# RGBW_LED-Band_Treiber_ungueltig.net
KiCad netlist of a schematic drawn in EAGLE
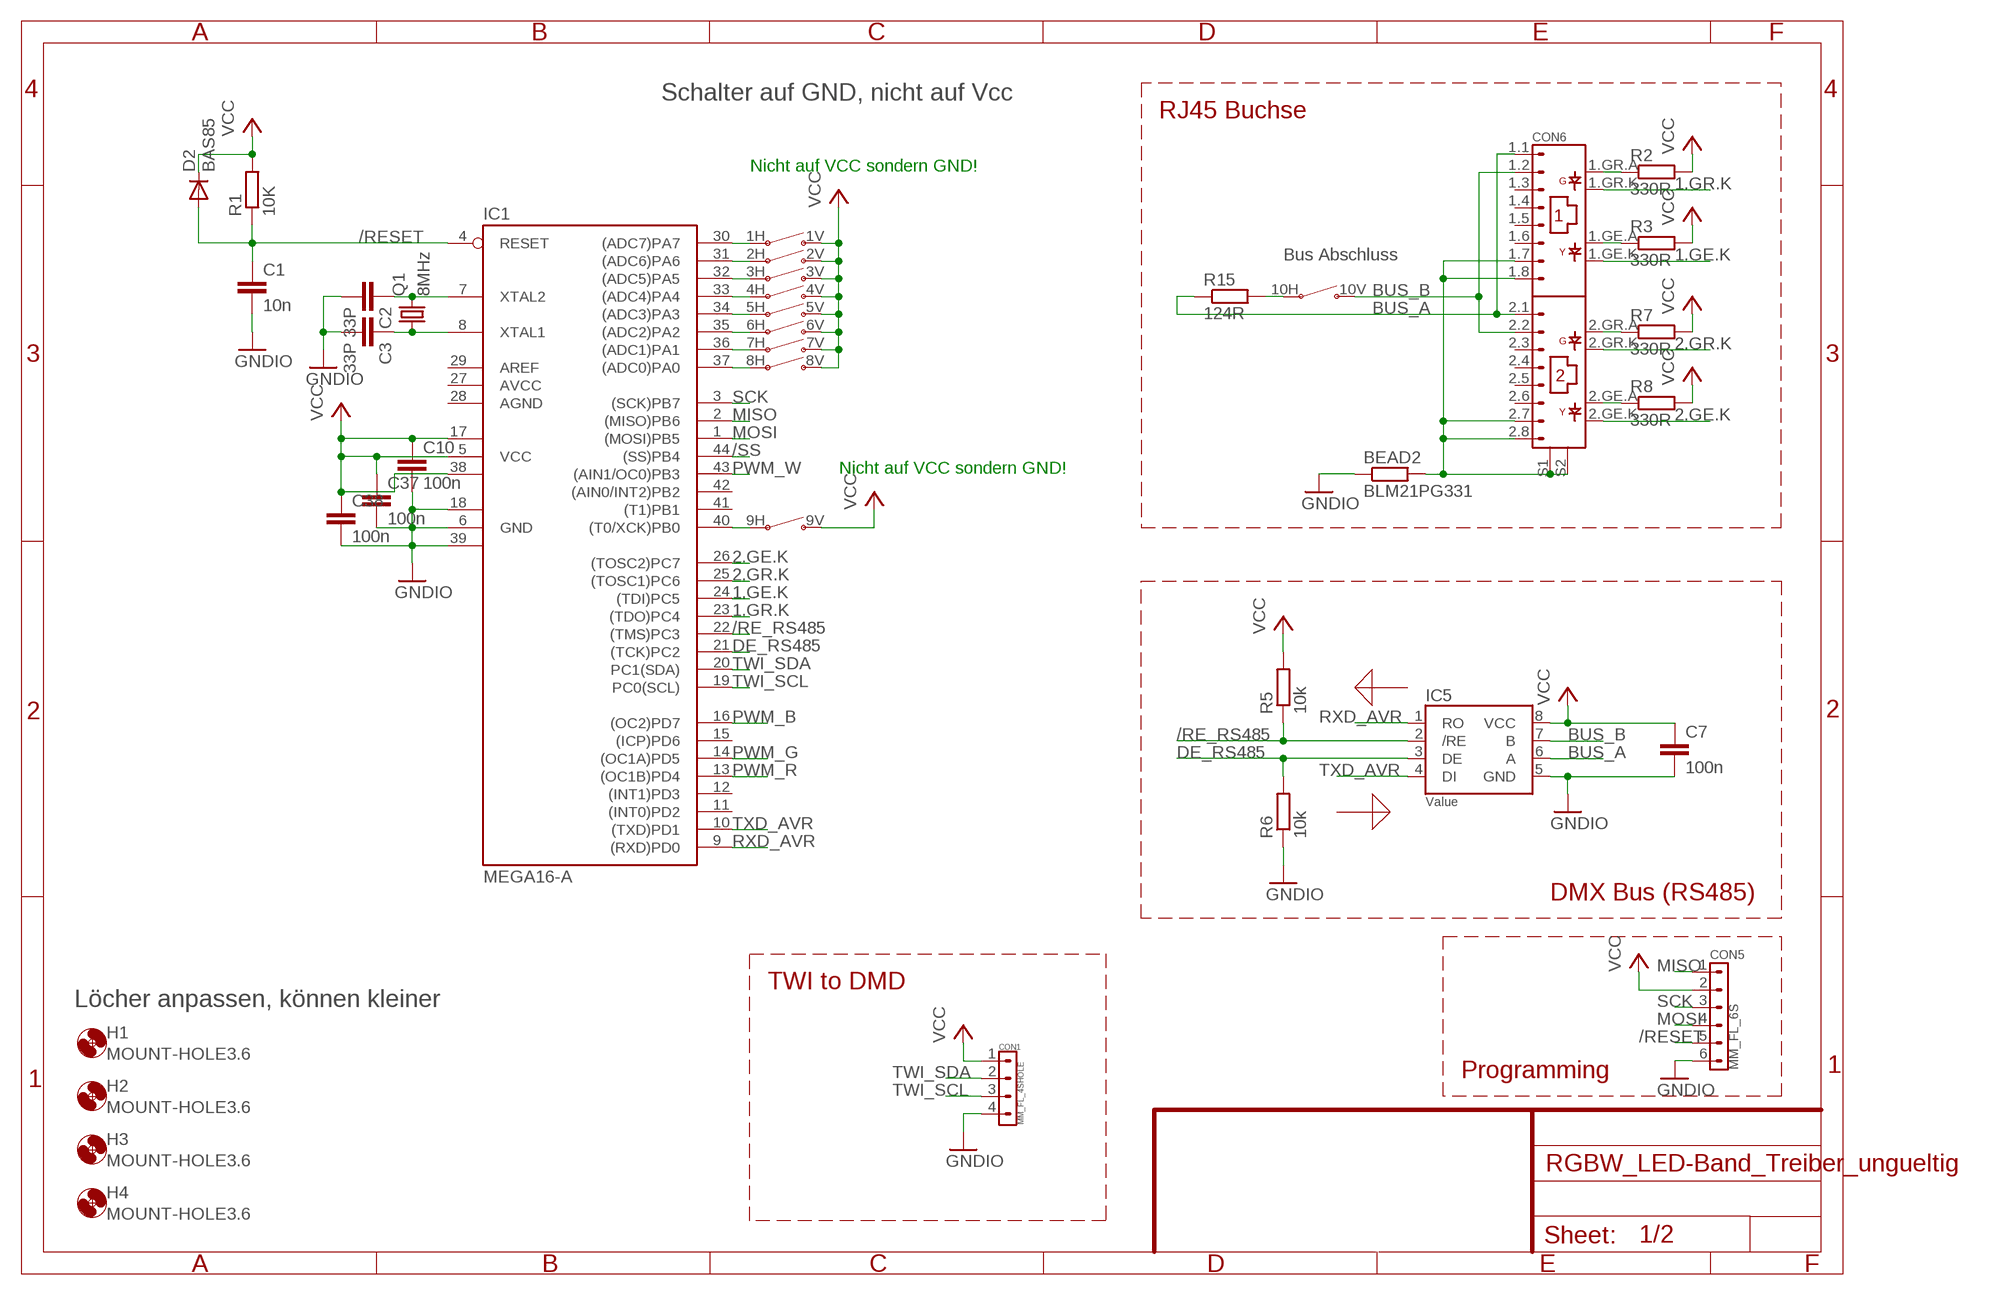
[diagram p0: schematic, sheet 1]
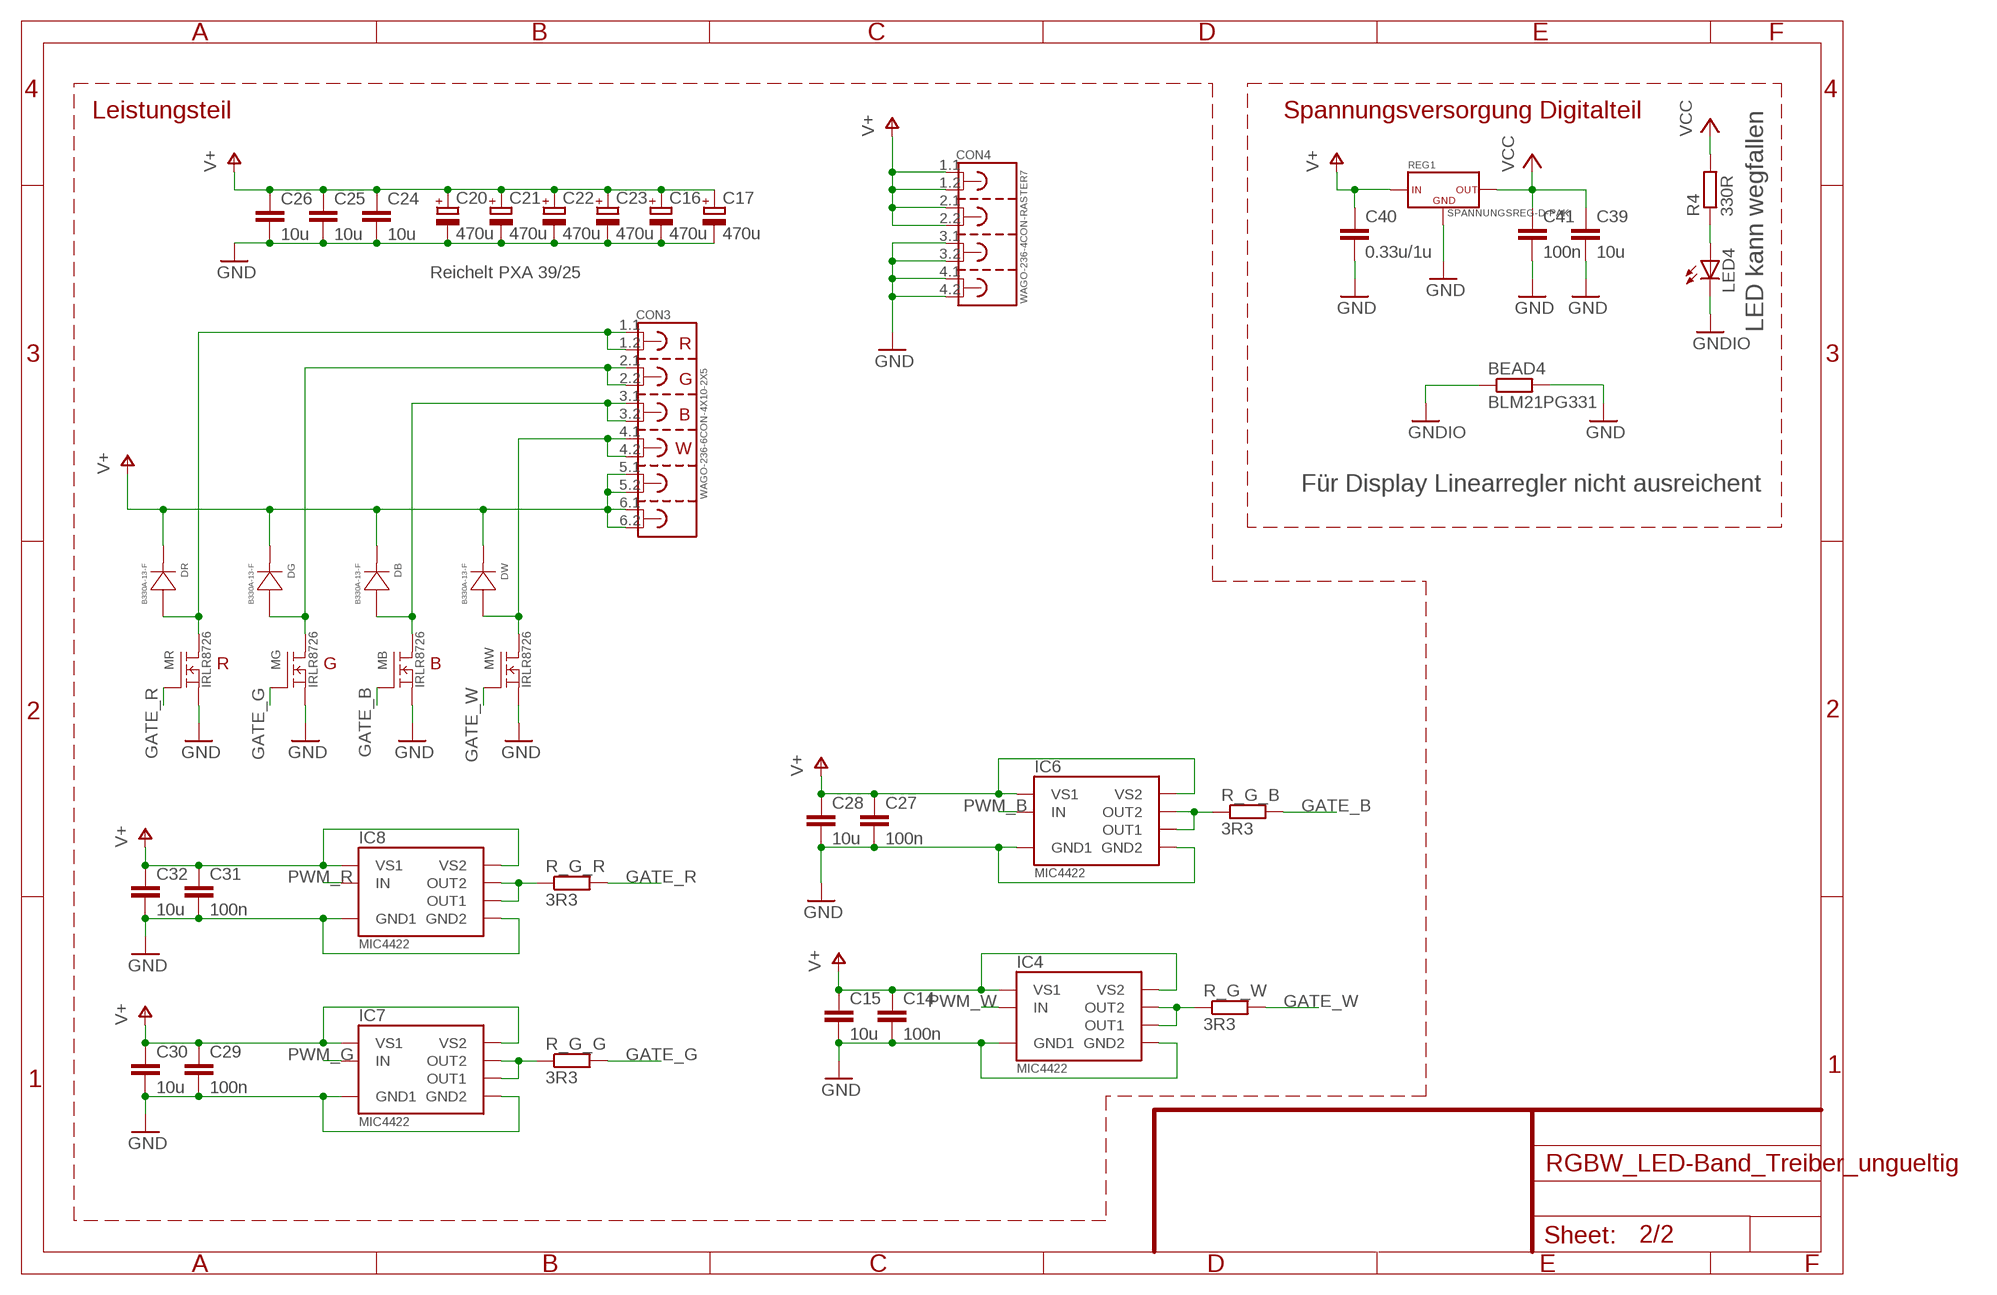
[diagram p1: schematic, sheet 2]

(export (version "E")
  (design (tool "Eeschema 10.0.6"))
  (components
    (comp (ref "BEAD2")
      (value "BLM21PG331")
      (footprint "eagle-import:R0805")
      (libsource (lib "eagle-import") (part "R-EU_R0805"))
    )
    (comp (ref "C1")
      (value "10n")
      (footprint "eagle-import:C0805")
      (libsource (lib "eagle-import") (part "C-EUC0805"))
    )
    (comp (ref "C2")
      (value "33P")
      (footprint "eagle-import:C0805")
      (libsource (lib "eagle-import") (part "C-EUC0805"))
    )
    (comp (ref "C3")
      (value "33P")
      (footprint "eagle-import:C0805")
      (libsource (lib "eagle-import") (part "C-EUC0805"))
    )
    (comp (ref "C7")
      (value "100n")
      (footprint "eagle-import:C0805")
      (libsource (lib "eagle-import") (part "C-EUC0805"))
    )
    (comp (ref "C10")
      (value "100n")
      (footprint "eagle-import:C0805")
      (libsource (lib "eagle-import") (part "C-EUC0805"))
    )
    (comp (ref "C37")
      (value "100n")
      (footprint "eagle-import:C0805")
      (libsource (lib "eagle-import") (part "C-EUC0805"))
    )
    (comp (ref "C38")
      (value "100n")
      (footprint "eagle-import:C0805")
      (libsource (lib "eagle-import") (part "C-EUC0805"))
    )
    (comp (ref "CON1")
      (value "MM_FL_4SHOLE")
      (footprint "eagle-import:MM_FL_4G")
      (libsource (lib "eagle-import") (part "MM_FL_4SHOLE"))
    )
    (comp (ref "CON5")
      (value "MM_FL_6S")
      (footprint "eagle-import:MM_FL_6G")
      (libsource (lib "eagle-import") (part "MM_FL_6STH"))
    )
    (comp (ref "CON6")
      (value "RJ45_2ER_LED")
      (footprint "eagle-import:RJ45_2ER_LED")
      (libsource (lib "eagle-import") (part "RJ45_2ER_LED"))
    )
    (comp (ref "D2")
      (value "BAS85")
      (footprint "eagle-import:SOD80C")
      (libsource (lib "eagle-import") (part "DIODE-SOD80C"))
    )
    (comp (ref "H1")
      (value "MOUNT-HOLE3.6")
      (footprint "eagle-import:3,6")
      (libsource (lib "eagle-import") (part "MOUNT-HOLE3.6"))
    )
    (comp (ref "H2")
      (value "MOUNT-HOLE3.6")
      (footprint "eagle-import:3,6")
      (libsource (lib "eagle-import") (part "MOUNT-HOLE3.6"))
    )
    (comp (ref "H3")
      (value "MOUNT-HOLE3.6")
      (footprint "eagle-import:3,6")
      (libsource (lib "eagle-import") (part "MOUNT-HOLE3.6"))
    )
    (comp (ref "H4")
      (value "MOUNT-HOLE3.6")
      (footprint "eagle-import:3,6")
      (libsource (lib "eagle-import") (part "MOUNT-HOLE3.6"))
    )
    (comp (ref "IC1")
      (value "MEGA16-A")
      (footprint "eagle-import:TQFP44")
      (libsource (lib "eagle-import") (part "MEGA16-A"))
    )
    (comp (ref "IC5")
      (value "LT1785")
      (footprint "eagle-import:SO08")
      (libsource (lib "eagle-import") (part "LT1785"))
    )
    (comp (ref "Q1")
      (value "8MHz")
      (footprint "eagle-import:HC49_S")
      (libsource (lib "eagle-import") (part "CRYTALHC49S"))
    )
    (comp (ref "R1")
      (value "10K")
      (footprint "eagle-import:R0805")
      (libsource (lib "eagle-import") (part "R-EU_R0805"))
    )
    (comp (ref "R2")
      (value "330R")
      (footprint "eagle-import:R0805")
      (libsource (lib "eagle-import") (part "R-EU_R0805"))
    )
    (comp (ref "R3")
      (value "330R")
      (footprint "eagle-import:R0805")
      (libsource (lib "eagle-import") (part "R-EU_R0805"))
    )
    (comp (ref "R5")
      (value "10k")
      (footprint "eagle-import:R0805")
      (libsource (lib "eagle-import") (part "R-EU_R0805"))
    )
    (comp (ref "R6")
      (value "10k")
      (footprint "eagle-import:R0805")
      (libsource (lib "eagle-import") (part "R-EU_R0805"))
    )
    (comp (ref "R7")
      (value "330R")
      (footprint "eagle-import:R0805")
      (libsource (lib "eagle-import") (part "R-EU_R0805"))
    )
    (comp (ref "R8")
      (value "330R")
      (footprint "eagle-import:R0805")
      (libsource (lib "eagle-import") (part "R-EU_R0805"))
    )
    (comp (ref "R15")
      (value "124R")
      (footprint "eagle-import:R0805")
      (libsource (lib "eagle-import") (part "R-EU_R0805"))
    )
    (comp (ref "S1")
      (value "DIP-SCHALTERPIANO")
      (footprint "eagle-import:DP_10")
      (libsource (lib "eagle-import") (part "DIP-SCHALTERPIANO"))
    )
    (comp (ref "BEAD4")
      (value "BLM21PG331")
      (footprint "eagle-import:R0805")
      (libsource (lib "eagle-import") (part "R-EU_R0805"))
    )
    (comp (ref "C14")
      (value "100n")
      (footprint "eagle-import:C0805")
      (libsource (lib "eagle-import") (part "C-EUC0805"))
    )
    (comp (ref "C15")
      (value "10u")
      (footprint "eagle-import:C0805")
      (libsource (lib "eagle-import") (part "C-EUC0805"))
    )
    (comp (ref "C16")
      (value "470u")
      (footprint "eagle-import:E5-10,5")
      (libsource (lib "eagle-import") (part "CPOL-EUE5-10.5"))
    )
    (comp (ref "C17")
      (value "470u")
      (footprint "eagle-import:E5-10,5")
      (libsource (lib "eagle-import") (part "CPOL-EUE5-10.5"))
    )
    (comp (ref "C20")
      (value "470u")
      (footprint "eagle-import:E5-10,5")
      (libsource (lib "eagle-import") (part "CPOL-EUE5-10.5"))
    )
    (comp (ref "C21")
      (value "470u")
      (footprint "eagle-import:E5-10,5")
      (libsource (lib "eagle-import") (part "CPOL-EUE5-10.5"))
    )
    (comp (ref "C22")
      (value "470u")
      (footprint "eagle-import:E5-10,5")
      (libsource (lib "eagle-import") (part "CPOL-EUE5-10.5"))
    )
    (comp (ref "C23")
      (value "470u")
      (footprint "eagle-import:E5-10,5")
      (libsource (lib "eagle-import") (part "CPOL-EUE5-10.5"))
    )
    (comp (ref "C24")
      (value "10u")
      (footprint "eagle-import:C0805")
      (libsource (lib "eagle-import") (part "C-EUC0805"))
    )
    (comp (ref "C25")
      (value "10u")
      (footprint "eagle-import:C0805")
      (libsource (lib "eagle-import") (part "C-EUC0805"))
    )
    (comp (ref "C26")
      (value "10u")
      (footprint "eagle-import:C0805")
      (libsource (lib "eagle-import") (part "C-EUC0805"))
    )
    (comp (ref "C27")
      (value "100n")
      (footprint "eagle-import:C0805")
      (libsource (lib "eagle-import") (part "C-EUC0805"))
    )
    (comp (ref "C28")
      (value "10u")
      (footprint "eagle-import:C0805")
      (libsource (lib "eagle-import") (part "C-EUC0805"))
    )
    (comp (ref "C29")
      (value "100n")
      (footprint "eagle-import:C0805")
      (libsource (lib "eagle-import") (part "C-EUC0805"))
    )
    (comp (ref "C30")
      (value "10u")
      (footprint "eagle-import:C0805")
      (libsource (lib "eagle-import") (part "C-EUC0805"))
    )
    (comp (ref "C31")
      (value "100n")
      (footprint "eagle-import:C0805")
      (libsource (lib "eagle-import") (part "C-EUC0805"))
    )
    (comp (ref "C32")
      (value "10u")
      (footprint "eagle-import:C0805")
      (libsource (lib "eagle-import") (part "C-EUC0805"))
    )
    (comp (ref "C39")
      (value "10u")
      (footprint "eagle-import:C0805")
      (libsource (lib "eagle-import") (part "C-EUC0805"))
    )
    (comp (ref "C40")
      (value "0.33u/1u")
      (footprint "eagle-import:C0805")
      (libsource (lib "eagle-import") (part "C-EUC0805"))
    )
    (comp (ref "C41")
      (value "100n")
      (footprint "eagle-import:C0805")
      (libsource (lib "eagle-import") (part "C-EUC0805"))
    )
    (comp (ref "CON3")
      (value "WAGO-236-6CON-4X10-2X5")
      (footprint "eagle-import:WAGO236_2X5_4X10")
      (libsource (lib "eagle-import") (part "WAGO-236-6CON-4X10-2X5"))
    )
    (comp (ref "CON4")
      (value "WAGO-236-4CON-RASTER7")
      (footprint "eagle-import:WAGO236_7.5_4")
      (libsource (lib "eagle-import") (part "WAGO-236-4CON-RASTER7"))
    )
    (comp (ref "DB")
      (value "B330A-13-F")
      (footprint "eagle-import:SMA")
      (libsource (lib "eagle-import") (part "B330A-13-F"))
    )
    (comp (ref "DG")
      (value "B330A-13-F")
      (footprint "eagle-import:SMA")
      (libsource (lib "eagle-import") (part "B330A-13-F"))
    )
    (comp (ref "DR")
      (value "B330A-13-F")
      (footprint "eagle-import:SMA")
      (libsource (lib "eagle-import") (part "B330A-13-F"))
    )
    (comp (ref "DW")
      (value "B330A-13-F")
      (footprint "eagle-import:SMA")
      (libsource (lib "eagle-import") (part "B330A-13-F"))
    )
    (comp (ref "IC4")
      (value "MIC4422")
      (footprint "eagle-import:SO08")
      (libsource (lib "eagle-import") (part "MIC4422"))
    )
    (comp (ref "IC6")
      (value "MIC4422")
      (footprint "eagle-import:SO08")
      (libsource (lib "eagle-import") (part "MIC4422"))
    )
    (comp (ref "IC7")
      (value "MIC4422")
      (footprint "eagle-import:SO08")
      (libsource (lib "eagle-import") (part "MIC4422"))
    )
    (comp (ref "IC8")
      (value "MIC4422")
      (footprint "eagle-import:SO08")
      (libsource (lib "eagle-import") (part "MIC4422"))
    )
    (comp (ref "LED4")
      (value "LEDCHIP-LED0805")
      (footprint "eagle-import:CHIP-LED0805")
      (libsource (lib "eagle-import") (part "LEDCHIP-LED0805"))
    )
    (comp (ref "MB")
      (value "IRLR8726")
      (footprint "eagle-import:D-PAK")
      (libsource (lib "eagle-import") (part "IRLR8726"))
    )
    (comp (ref "MG")
      (value "IRLR8726")
      (footprint "eagle-import:D-PAK")
      (libsource (lib "eagle-import") (part "IRLR8726"))
    )
    (comp (ref "MR")
      (value "IRLR8726")
      (footprint "eagle-import:D-PAK")
      (libsource (lib "eagle-import") (part "IRLR8726"))
    )
    (comp (ref "MW")
      (value "IRLR8726")
      (footprint "eagle-import:D-PAK")
      (libsource (lib "eagle-import") (part "IRLR8726"))
    )
    (comp (ref "R4")
      (value "330R")
      (footprint "eagle-import:R0805")
      (libsource (lib "eagle-import") (part "R-EU_R0805"))
    )
    (comp (ref "REG1")
      (value "SPANNUNGSREG-D-PAK")
      (footprint "eagle-import:D-PAK")
      (libsource (lib "eagle-import") (part "SPANNUNGSREG-D-PAK"))
    )
    (comp (ref "R_G_B")
      (value "3R3")
      (footprint "eagle-import:R0805")
      (libsource (lib "eagle-import") (part "R-EU_R0805"))
    )
    (comp (ref "R_G_G")
      (value "3R3")
      (footprint "eagle-import:R0805")
      (libsource (lib "eagle-import") (part "R-EU_R0805"))
    )
    (comp (ref "R_G_R")
      (value "3R3")
      (footprint "eagle-import:R0805")
      (libsource (lib "eagle-import") (part "R-EU_R0805"))
    )
    (comp (ref "R_G_W")
      (value "3R3")
      (footprint "eagle-import:R0805")
      (libsource (lib "eagle-import") (part "R-EU_R0805"))
    )
  )
  (nets
    (net (code "1") (name "1.GE.K") (class "Default")
      (node (ref "CON6") (pin "1.GE.K") (pinfunction "1.GE.K_1.GE.K") (pintype "bidirectional"))
      (node (ref "IC1") (pin "24") (pinfunction "(TDI)PC5_24") (pintype "bidirectional"))
    )
    (net (code "2") (name "1.GR.K") (class "Default")
      (node (ref "CON6") (pin "1.GR.K") (pinfunction "1.GR.K_1.GR.K") (pintype "bidirectional"))
      (node (ref "IC1") (pin "23") (pinfunction "(TDO)PC4_23") (pintype "bidirectional"))
    )
    (net (code "3") (name "2.GE.K") (class "Default")
      (node (ref "CON6") (pin "2.GE.K") (pinfunction "2.GE.K_2.GE.K") (pintype "bidirectional"))
      (node (ref "IC1") (pin "26") (pinfunction "(TOSC2)PC7_26") (pintype "bidirectional"))
    )
    (net (code "4") (name "2.GR.K") (class "Default")
      (node (ref "CON6") (pin "2.GR.K") (pinfunction "2.GR.K_2.GR.K") (pintype "bidirectional"))
      (node (ref "IC1") (pin "25") (pinfunction "(TOSC1)PC6_25") (pintype "bidirectional"))
    )
    (net (code "5") (name "AGND") (class "Default")
      (node (ref "IC1") (pin "28") (pinfunction "AGND_28") (pintype "power_in"))
    )
    (net (code "6") (name "AREF") (class "Default")
      (node (ref "IC1") (pin "29") (pinfunction "AREF_29") (pintype "power_in"))
    )
    (net (code "7") (name "AVCC") (class "Default")
      (node (ref "IC1") (pin "27") (pinfunction "AVCC_27") (pintype "power_in"))
    )
    (net (code "8") (name "BUS_A") (class "Default")
      (node (ref "CON6") (pin "1.1") (pinfunction "1.1_1.1") (pintype "bidirectional"))
      (node (ref "CON6") (pin "2.1") (pinfunction "2.1_2.1") (pintype "bidirectional"))
      (node (ref "IC5") (pin "6") (pinfunction "A_6") (pintype "bidirectional"))
      (node (ref "R15") (pin "1") (pinfunction "1_1") (pintype "passive"))
    )
    (net (code "9") (name "BUS_B") (class "Default")
      (node (ref "CON6") (pin "1.2") (pinfunction "1.2_1.2") (pintype "bidirectional"))
      (node (ref "CON6") (pin "2.2") (pinfunction "2.2_2.2") (pintype "bidirectional"))
      (node (ref "IC5") (pin "7") (pinfunction "B_7") (pintype "bidirectional"))
      (node (ref "S1") (pin "10V") (pinfunction "P$2_10V") (pintype "bidirectional"))
    )
    (net (code "10") (name "DE_RS485") (class "Default")
      (node (ref "IC1") (pin "21") (pinfunction "(TCK)PC2_21") (pintype "bidirectional"))
      (node (ref "IC5") (pin "3") (pinfunction "DE_3") (pintype "bidirectional"))
      (node (ref "R6") (pin "2") (pinfunction "2_2") (pintype "passive"))
    )
    (net (code "11") (name "GATE_B") (class "Default")
      (node (ref "MB") (pin "G") (pinfunction "G_G") (pintype "bidirectional"))
      (node (ref "R_G_B") (pin "2") (pinfunction "2_2") (pintype "passive"))
    )
    (net (code "12") (name "GATE_G") (class "Default")
      (node (ref "MG") (pin "G") (pinfunction "G_G") (pintype "bidirectional"))
      (node (ref "R_G_G") (pin "2") (pinfunction "2_2") (pintype "passive"))
    )
    (net (code "13") (name "GATE_R") (class "Default")
      (node (ref "MR") (pin "G") (pinfunction "G_G") (pintype "bidirectional"))
      (node (ref "R_G_R") (pin "2") (pinfunction "2_2") (pintype "passive"))
    )
    (net (code "14") (name "GATE_W") (class "Default")
      (node (ref "MW") (pin "G") (pinfunction "G_G") (pintype "bidirectional"))
      (node (ref "R_G_W") (pin "2") (pinfunction "2_2") (pintype "passive"))
    )
    (net (code "15") (name "GND") (class "Default")
      (node (ref "BEAD4") (pin "2") (pinfunction "2_2") (pintype "passive"))
      (node (ref "C14") (pin "2") (pinfunction "2_2") (pintype "passive"))
      (node (ref "C15") (pin "2") (pinfunction "2_2") (pintype "passive"))
      (node (ref "C16") (pin "-") (pinfunction "-_-") (pintype "passive"))
      (node (ref "C17") (pin "-") (pinfunction "-_-") (pintype "passive"))
      (node (ref "C20") (pin "-") (pinfunction "-_-") (pintype "passive"))
      (node (ref "C21") (pin "-") (pinfunction "-_-") (pintype "passive"))
      (node (ref "C22") (pin "-") (pinfunction "-_-") (pintype "passive"))
      (node (ref "C23") (pin "-") (pinfunction "-_-") (pintype "passive"))
      (node (ref "C24") (pin "2") (pinfunction "2_2") (pintype "passive"))
      (node (ref "C25") (pin "2") (pinfunction "2_2") (pintype "passive"))
      (node (ref "C26") (pin "2") (pinfunction "2_2") (pintype "passive"))
      (node (ref "C27") (pin "2") (pinfunction "2_2") (pintype "passive"))
      (node (ref "C28") (pin "2") (pinfunction "2_2") (pintype "passive"))
      (node (ref "C29") (pin "2") (pinfunction "2_2") (pintype "passive"))
      (node (ref "C30") (pin "2") (pinfunction "2_2") (pintype "passive"))
      (node (ref "C31") (pin "2") (pinfunction "2_2") (pintype "passive"))
      (node (ref "C32") (pin "2") (pinfunction "2_2") (pintype "passive"))
      (node (ref "C39") (pin "2") (pinfunction "2_2") (pintype "passive"))
      (node (ref "C40") (pin "2") (pinfunction "2_2") (pintype "passive"))
      (node (ref "C41") (pin "2") (pinfunction "2_2") (pintype "passive"))
      (node (ref "CON4") (pin "3.1") (pinfunction "P$5_3.1") (pintype "bidirectional"))
      (node (ref "CON4") (pin "3.2") (pinfunction "P$6_3.2") (pintype "bidirectional"))
      (node (ref "CON4") (pin "4.1") (pinfunction "P$7_4.1") (pintype "bidirectional"))
      (node (ref "CON4") (pin "4.2") (pinfunction "P$8_4.2") (pintype "bidirectional"))
      (node (ref "IC4") (pin "4") (pinfunction "GND1_4") (pintype "bidirectional"))
      (node (ref "IC4") (pin "5") (pinfunction "GND2_5") (pintype "bidirectional"))
      (node (ref "IC6") (pin "4") (pinfunction "GND1_4") (pintype "bidirectional"))
      (node (ref "IC6") (pin "5") (pinfunction "GND2_5") (pintype "bidirectional"))
      (node (ref "IC7") (pin "4") (pinfunction "GND1_4") (pintype "bidirectional"))
      (node (ref "IC7") (pin "5") (pinfunction "GND2_5") (pintype "bidirectional"))
      (node (ref "IC8") (pin "4") (pinfunction "GND1_4") (pintype "bidirectional"))
      (node (ref "IC8") (pin "5") (pinfunction "GND2_5") (pintype "bidirectional"))
      (node (ref "MB") (pin "S") (pinfunction "S_S") (pintype "bidirectional"))
      (node (ref "MG") (pin "S") (pinfunction "S_S") (pintype "bidirectional"))
      (node (ref "MR") (pin "S") (pinfunction "S_S") (pintype "bidirectional"))
      (node (ref "MW") (pin "S") (pinfunction "S_S") (pintype "bidirectional"))
      (node (ref "REG1") (pin "D") (pinfunction "GND_D") (pintype "bidirectional"))
    )
    (net (code "16") (name "GNDIO") (class "Default")
      (node (ref "BEAD2") (pin "1") (pinfunction "1_1") (pintype "passive"))
      (node (ref "BEAD4") (pin "1") (pinfunction "1_1") (pintype "passive"))
      (node (ref "C1") (pin "2") (pinfunction "2_2") (pintype "passive"))
      (node (ref "C10") (pin "2") (pinfunction "2_2") (pintype "passive"))
      (node (ref "C2") (pin "2") (pinfunction "2_2") (pintype "passive"))
      (node (ref "C3") (pin "2") (pinfunction "2_2") (pintype "passive"))
      (node (ref "C37") (pin "2") (pinfunction "2_2") (pintype "passive"))
      (node (ref "C38") (pin "2") (pinfunction "2_2") (pintype "passive"))
      (node (ref "C7") (pin "2") (pinfunction "2_2") (pintype "passive"))
      (node (ref "CON1") (pin "4") (pinfunction "P$4_4") (pintype "bidirectional"))
      (node (ref "CON5") (pin "6") (pinfunction "P$6_6") (pintype "bidirectional"))
      (node (ref "IC1") (pin "18") (pinfunction "GND1_18") (pintype "power_in"))
      (node (ref "IC1") (pin "39") (pinfunction "GND2_39") (pintype "power_in"))
      (node (ref "IC1") (pin "6") (pinfunction "GND_6") (pintype "power_in"))
      (node (ref "IC5") (pin "5") (pinfunction "GND_5") (pintype "bidirectional"))
      (node (ref "LED4") (pin "C") (pinfunction "C_C") (pintype "passive"))
      (node (ref "R6") (pin "1") (pinfunction "1_1") (pintype "passive"))
    )
    (net (code "17") (name "MISO") (class "Default")
      (node (ref "CON5") (pin "1") (pinfunction "P$1_1") (pintype "bidirectional"))
      (node (ref "IC1") (pin "2") (pinfunction "(MISO)PB6_2") (pintype "bidirectional"))
    )
    (net (code "18") (name "MOSI") (class "Default")
      (node (ref "CON5") (pin "4") (pinfunction "P$4_4") (pintype "bidirectional"))
      (node (ref "IC1") (pin "1") (pinfunction "(MOSI)PB5_1") (pintype "bidirectional"))
    )
    (net (code "19") (name "Net-(BEAD2-Pad2)") (class "Default")
      (node (ref "BEAD2") (pin "2") (pinfunction "2_2") (pintype "passive"))
      (node (ref "CON6") (pin "1.7") (pinfunction "1.7_1.7") (pintype "bidirectional"))
      (node (ref "CON6") (pin "1.8") (pinfunction "1.8_1.8") (pintype "bidirectional"))
      (node (ref "CON6") (pin "2.7") (pinfunction "2.7_2.7") (pintype "bidirectional"))
      (node (ref "CON6") (pin "2.8") (pinfunction "2.8_2.8") (pintype "bidirectional"))
      (node (ref "CON6") (pin "S1") (pinfunction "S1_S1") (pintype "bidirectional"))
      (node (ref "CON6") (pin "S2") (pinfunction "S2_S2") (pintype "bidirectional"))
    )
    (net (code "20") (name "Net-(CON3-3.3)") (class "Default")
      (node (ref "CON3") (pin "3.1") (pinfunction "3.1_3.1") (pintype "bidirectional"))
      (node (ref "CON3") (pin "3.2") (pinfunction "3.3_3.2") (pintype "bidirectional"))
      (node (ref "DB") (pin "A") (pinfunction "A_A") (pintype "bidirectional"))
      (node (ref "MB") (pin "D") (pinfunction "D_D") (pintype "bidirectional"))
    )
    (net (code "21") (name "Net-(CON3-Pad1.1)") (class "Default")
      (node (ref "CON3") (pin "1.1") (pinfunction "1.1_1.1") (pintype "bidirectional"))
      (node (ref "CON3") (pin "1.2") (pinfunction "1.2_1.2") (pintype "bidirectional"))
      (node (ref "DR") (pin "A") (pinfunction "A_A") (pintype "bidirectional"))
      (node (ref "MR") (pin "D") (pinfunction "D_D") (pintype "bidirectional"))
    )
    (net (code "22") (name "Net-(CON3-Pad2.1)") (class "Default")
      (node (ref "CON3") (pin "2.1") (pinfunction "2.1_2.1") (pintype "bidirectional"))
      (node (ref "CON3") (pin "2.2") (pinfunction "2.2_2.2") (pintype "bidirectional"))
      (node (ref "DG") (pin "A") (pinfunction "A_A") (pintype "bidirectional"))
      (node (ref "MG") (pin "D") (pinfunction "D_D") (pintype "bidirectional"))
    )
    (net (code "23") (name "Net-(CON3-Pad4.1)") (class "Default")
      (node (ref "CON3") (pin "4.1") (pinfunction "4.1_4.1") (pintype "bidirectional"))
      (node (ref "CON3") (pin "4.2") (pinfunction "4.2_4.2") (pintype "bidirectional"))
      (node (ref "DW") (pin "A") (pinfunction "A_A") (pintype "bidirectional"))
      (node (ref "MW") (pin "D") (pinfunction "D_D") (pintype "bidirectional"))
    )
    (net (code "24") (name "Net-(CON6-Pad1.GE.A)") (class "Default")
      (node (ref "CON6") (pin "1.GE.A") (pinfunction "1.GE.A_1.GE.A") (pintype "bidirectional"))
      (node (ref "R3") (pin "1") (pinfunction "1_1") (pintype "passive"))
    )
    (net (code "25") (name "Net-(CON6-Pad1.GR.A)") (class "Default")
      (node (ref "CON6") (pin "1.GR.A") (pinfunction "1.GR.A_1.GR.A") (pintype "bidirectional"))
      (node (ref "R2") (pin "1") (pinfunction "1_1") (pintype "passive"))
    )
    (net (code "26") (name "Net-(CON6-Pad2.GE.A)") (class "Default")
      (node (ref "CON6") (pin "2.GE.A") (pinfunction "2.GE.A_2.GE.A") (pintype "bidirectional"))
      (node (ref "R8") (pin "1") (pinfunction "1_1") (pintype "passive"))
    )
    (net (code "27") (name "Net-(CON6-Pad2.GR.A)") (class "Default")
      (node (ref "CON6") (pin "2.GR.A") (pinfunction "2.GR.A_2.GR.A") (pintype "bidirectional"))
      (node (ref "R7") (pin "1") (pinfunction "1_1") (pintype "passive"))
    )
    (net (code "28") (name "Net-(IC1-(ADC0)PA0)") (class "Default")
      (node (ref "IC1") (pin "37") (pinfunction "(ADC0)PA0_37") (pintype "bidirectional"))
      (node (ref "S1") (pin "8H") (pinfunction "P$1_8H") (pintype "bidirectional"))
    )
    (net (code "29") (name "Net-(IC1-(ADC1)PA1)") (class "Default")
      (node (ref "IC1") (pin "36") (pinfunction "(ADC1)PA1_36") (pintype "bidirectional"))
      (node (ref "S1") (pin "7H") (pinfunction "P$1_7H") (pintype "bidirectional"))
    )
    (net (code "30") (name "Net-(IC1-(ADC2)PA2)") (class "Default")
      (node (ref "IC1") (pin "35") (pinfunction "(ADC2)PA2_35") (pintype "bidirectional"))
      (node (ref "S1") (pin "6H") (pinfunction "P$1_6H") (pintype "bidirectional"))
    )
    (net (code "31") (name "Net-(IC1-(ADC3)PA3)") (class "Default")
      (node (ref "IC1") (pin "34") (pinfunction "(ADC3)PA3_34") (pintype "bidirectional"))
      (node (ref "S1") (pin "5H") (pinfunction "P$1_5H") (pintype "bidirectional"))
    )
    (net (code "32") (name "Net-(IC1-(ADC4)PA4)") (class "Default")
      (node (ref "IC1") (pin "33") (pinfunction "(ADC4)PA4_33") (pintype "bidirectional"))
      (node (ref "S1") (pin "4H") (pinfunction "P$1_4H") (pintype "bidirectional"))
    )
    (net (code "33") (name "Net-(IC1-(ADC5)PA5)") (class "Default")
      (node (ref "IC1") (pin "32") (pinfunction "(ADC5)PA5_32") (pintype "bidirectional"))
      (node (ref "S1") (pin "3H") (pinfunction "P$1_3H") (pintype "bidirectional"))
    )
    (net (code "34") (name "Net-(IC1-(ADC6)PA6)") (class "Default")
      (node (ref "IC1") (pin "31") (pinfunction "(ADC6)PA6_31") (pintype "bidirectional"))
      (node (ref "S1") (pin "2H") (pinfunction "P$1_2H") (pintype "bidirectional"))
    )
    (net (code "35") (name "Net-(IC1-(ADC7)PA7)") (class "Default")
      (node (ref "IC1") (pin "30") (pinfunction "(ADC7)PA7_30") (pintype "bidirectional"))
      (node (ref "S1") (pin "1H") (pinfunction "P$1_1H") (pintype "bidirectional"))
    )
    (net (code "36") (name "Net-(IC1-(T0{slash}XCK)PB0)") (class "Default")
      (node (ref "IC1") (pin "40") (pinfunction "(T0/XCK)PB0_40") (pintype "bidirectional"))
      (node (ref "S1") (pin "9H") (pinfunction "P$1_9H") (pintype "bidirectional"))
    )
    (net (code "37") (name "Net-(IC1-XTAL1)") (class "Default")
      (node (ref "C3") (pin "1") (pinfunction "1_1") (pintype "passive"))
      (node (ref "IC1") (pin "8") (pinfunction "XTAL1_8") (pintype "bidirectional"))
      (node (ref "Q1") (pin "1") (pinfunction "1_1") (pintype "passive"))
    )
    (net (code "38") (name "Net-(IC1-XTAL2)") (class "Default")
      (node (ref "C2") (pin "1") (pinfunction "1_1") (pintype "passive"))
      (node (ref "IC1") (pin "7") (pinfunction "XTAL2_7") (pintype "bidirectional"))
      (node (ref "Q1") (pin "2") (pinfunction "2_2") (pintype "passive"))
    )
    (net (code "39") (name "Net-(IC4-OUT1)") (class "Default")
      (node (ref "IC4") (pin "6") (pinfunction "OUT1_6") (pintype "bidirectional"))
      (node (ref "IC4") (pin "7") (pinfunction "OUT2_7") (pintype "bidirectional"))
      (node (ref "R_G_W") (pin "1") (pinfunction "1_1") (pintype "passive"))
    )
    (net (code "40") (name "Net-(IC6-OUT1)") (class "Default")
      (node (ref "IC6") (pin "6") (pinfunction "OUT1_6") (pintype "bidirectional"))
      (node (ref "IC6") (pin "7") (pinfunction "OUT2_7") (pintype "bidirectional"))
      (node (ref "R_G_B") (pin "1") (pinfunction "1_1") (pintype "passive"))
    )
    (net (code "41") (name "Net-(IC7-OUT1)") (class "Default")
      (node (ref "IC7") (pin "6") (pinfunction "OUT1_6") (pintype "bidirectional"))
      (node (ref "IC7") (pin "7") (pinfunction "OUT2_7") (pintype "bidirectional"))
      (node (ref "R_G_G") (pin "1") (pinfunction "1_1") (pintype "passive"))
    )
    (net (code "42") (name "Net-(IC8-OUT1)") (class "Default")
      (node (ref "IC8") (pin "6") (pinfunction "OUT1_6") (pintype "bidirectional"))
      (node (ref "IC8") (pin "7") (pinfunction "OUT2_7") (pintype "bidirectional"))
      (node (ref "R_G_R") (pin "1") (pinfunction "1_1") (pintype "passive"))
    )
    (net (code "43") (name "Net-(LED4-PadA)") (class "Default")
      (node (ref "LED4") (pin "A") (pinfunction "A_A") (pintype "passive"))
      (node (ref "R4") (pin "1") (pinfunction "1_1") (pintype "passive"))
    )
    (net (code "44") (name "Net-(S1B-P$1)") (class "Default")
      (node (ref "R15") (pin "2") (pinfunction "2_2") (pintype "passive"))
      (node (ref "S1") (pin "10H") (pinfunction "P$1_10H") (pintype "bidirectional"))
    )
    (net (code "45") (name "PWM_B") (class "Default")
      (node (ref "IC1") (pin "16") (pinfunction "(OC2)PD7_16") (pintype "bidirectional"))
      (node (ref "IC6") (pin "2") (pinfunction "IN_2") (pintype "bidirectional"))
    )
    (net (code "46") (name "PWM_G") (class "Default")
      (node (ref "IC1") (pin "14") (pinfunction "(OC1A)PD5_14") (pintype "bidirectional"))
      (node (ref "IC7") (pin "2") (pinfunction "IN_2") (pintype "bidirectional"))
    )
    (net (code "47") (name "PWM_R") (class "Default")
      (node (ref "IC1") (pin "13") (pinfunction "(OC1B)PD4_13") (pintype "bidirectional"))
      (node (ref "IC8") (pin "2") (pinfunction "IN_2") (pintype "bidirectional"))
    )
    (net (code "48") (name "PWM_W") (class "Default")
      (node (ref "IC1") (pin "43") (pinfunction "(AIN1/OC0)PB3_43") (pintype "bidirectional"))
      (node (ref "IC4") (pin "2") (pinfunction "IN_2") (pintype "bidirectional"))
    )
    (net (code "49") (name "RXD_AVR") (class "Default")
      (node (ref "IC1") (pin "9") (pinfunction "(RXD)PD0_9") (pintype "bidirectional"))
      (node (ref "IC5") (pin "1") (pinfunction "RO_1") (pintype "bidirectional"))
    )
    (net (code "50") (name "SCK") (class "Default")
      (node (ref "CON5") (pin "3") (pinfunction "P$3_3") (pintype "bidirectional"))
      (node (ref "IC1") (pin "3") (pinfunction "(SCK)PB7_3") (pintype "bidirectional"))
    )
    (net (code "51") (name "TWI_SCL") (class "Default")
      (node (ref "CON1") (pin "3") (pinfunction "P$3_3") (pintype "bidirectional"))
      (node (ref "IC1") (pin "19") (pinfunction "PC0(SCL)_19") (pintype "bidirectional"))
    )
    (net (code "52") (name "TWI_SDA") (class "Default")
      (node (ref "CON1") (pin "2") (pinfunction "P$2_2") (pintype "bidirectional"))
      (node (ref "IC1") (pin "20") (pinfunction "PC1(SDA)_20") (pintype "bidirectional"))
    )
    (net (code "53") (name "TXD_AVR") (class "Default")
      (node (ref "IC1") (pin "10") (pinfunction "(TXD)PD1_10") (pintype "bidirectional"))
      (node (ref "IC5") (pin "4") (pinfunction "DI_4") (pintype "bidirectional"))
    )
    (net (code "54") (name "V+") (class "Default")
      (node (ref "C14") (pin "1") (pinfunction "1_1") (pintype "passive"))
      (node (ref "C15") (pin "1") (pinfunction "1_1") (pintype "passive"))
      (node (ref "C16") (pin "+") (pinfunction "+_+") (pintype "passive"))
      (node (ref "C17") (pin "+") (pinfunction "+_+") (pintype "passive"))
      (node (ref "C20") (pin "+") (pinfunction "+_+") (pintype "passive"))
      (node (ref "C21") (pin "+") (pinfunction "+_+") (pintype "passive"))
      (node (ref "C22") (pin "+") (pinfunction "+_+") (pintype "passive"))
      (node (ref "C23") (pin "+") (pinfunction "+_+") (pintype "passive"))
      (node (ref "C24") (pin "1") (pinfunction "1_1") (pintype "passive"))
      (node (ref "C25") (pin "1") (pinfunction "1_1") (pintype "passive"))
      (node (ref "C26") (pin "1") (pinfunction "1_1") (pintype "passive"))
      (node (ref "C27") (pin "1") (pinfunction "1_1") (pintype "passive"))
      (node (ref "C28") (pin "1") (pinfunction "1_1") (pintype "passive"))
      (node (ref "C29") (pin "1") (pinfunction "1_1") (pintype "passive"))
      (node (ref "C30") (pin "1") (pinfunction "1_1") (pintype "passive"))
      (node (ref "C31") (pin "1") (pinfunction "1_1") (pintype "passive"))
      (node (ref "C32") (pin "1") (pinfunction "1_1") (pintype "passive"))
      (node (ref "C40") (pin "1") (pinfunction "1_1") (pintype "passive"))
      (node (ref "CON3") (pin "5.1") (pinfunction "5.1_5.1") (pintype "bidirectional"))
      (node (ref "CON3") (pin "5.2") (pinfunction "5.2_5.2") (pintype "bidirectional"))
      (node (ref "CON3") (pin "6.1") (pinfunction "6.1_6.1") (pintype "bidirectional"))
      (node (ref "CON3") (pin "6.2") (pinfunction "6.2_6.2") (pintype "bidirectional"))
      (node (ref "CON4") (pin "1.1") (pinfunction "P$1_1.1") (pintype "bidirectional"))
      (node (ref "CON4") (pin "1.2") (pinfunction "P$2_1.2") (pintype "bidirectional"))
      (node (ref "CON4") (pin "2.1") (pinfunction "P$3_2.1") (pintype "bidirectional"))
      (node (ref "CON4") (pin "2.2") (pinfunction "P$4_2.2") (pintype "bidirectional"))
      (node (ref "DB") (pin "K") (pinfunction "K_K") (pintype "bidirectional"))
      (node (ref "DG") (pin "K") (pinfunction "K_K") (pintype "bidirectional"))
      (node (ref "DR") (pin "K") (pinfunction "K_K") (pintype "bidirectional"))
      (node (ref "DW") (pin "K") (pinfunction "K_K") (pintype "bidirectional"))
      (node (ref "IC4") (pin "1") (pinfunction "VS1_1") (pintype "bidirectional"))
      (node (ref "IC4") (pin "8") (pinfunction "VS2_8") (pintype "bidirectional"))
      (node (ref "IC6") (pin "1") (pinfunction "VS1_1") (pintype "bidirectional"))
      (node (ref "IC6") (pin "8") (pinfunction "VS2_8") (pintype "bidirectional"))
      (node (ref "IC7") (pin "1") (pinfunction "VS1_1") (pintype "bidirectional"))
      (node (ref "IC7") (pin "8") (pinfunction "VS2_8") (pintype "bidirectional"))
      (node (ref "IC8") (pin "1") (pinfunction "VS1_1") (pintype "bidirectional"))
      (node (ref "IC8") (pin "8") (pinfunction "VS2_8") (pintype "bidirectional"))
      (node (ref "REG1") (pin "G") (pinfunction "IN_G") (pintype "bidirectional"))
    )
    (net (code "55") (name "VCC") (class "Default")
      (node (ref "C10") (pin "1") (pinfunction "1_1") (pintype "passive"))
      (node (ref "C37") (pin "1") (pinfunction "1_1") (pintype "passive"))
      (node (ref "C38") (pin "1") (pinfunction "1_1") (pintype "passive"))
      (node (ref "C39") (pin "1") (pinfunction "1_1") (pintype "passive"))
      (node (ref "C41") (pin "1") (pinfunction "1_1") (pintype "passive"))
      (node (ref "C7") (pin "1") (pinfunction "1_1") (pintype "passive"))
      (node (ref "CON1") (pin "1") (pinfunction "P$1_1") (pintype "bidirectional"))
      (node (ref "CON5") (pin "2") (pinfunction "P$2_2") (pintype "bidirectional"))
      (node (ref "D2") (pin "C") (pinfunction "C_C") (pintype "passive"))
      (node (ref "IC1") (pin "17") (pinfunction "VCC1_17") (pintype "power_in"))
      (node (ref "IC1") (pin "38") (pinfunction "VCC2_38") (pintype "power_in"))
      (node (ref "IC1") (pin "5") (pinfunction "VCC_5") (pintype "power_in"))
      (node (ref "IC5") (pin "8") (pinfunction "VCC_8") (pintype "bidirectional"))
      (node (ref "R1") (pin "2") (pinfunction "2_2") (pintype "passive"))
      (node (ref "R2") (pin "2") (pinfunction "2_2") (pintype "passive"))
      (node (ref "R3") (pin "2") (pinfunction "2_2") (pintype "passive"))
      (node (ref "R4") (pin "2") (pinfunction "2_2") (pintype "passive"))
      (node (ref "R5") (pin "2") (pinfunction "2_2") (pintype "passive"))
      (node (ref "R7") (pin "2") (pinfunction "2_2") (pintype "passive"))
      (node (ref "R8") (pin "2") (pinfunction "2_2") (pintype "passive"))
      (node (ref "REG1") (pin "S") (pinfunction "OUT_S") (pintype "bidirectional"))
      (node (ref "S1") (pin "1V") (pinfunction "P$2_1V") (pintype "bidirectional"))
      (node (ref "S1") (pin "2V") (pinfunction "P$2_2V") (pintype "bidirectional"))
      (node (ref "S1") (pin "3V") (pinfunction "P$2_3V") (pintype "bidirectional"))
      (node (ref "S1") (pin "4V") (pinfunction "P$2_4V") (pintype "bidirectional"))
      (node (ref "S1") (pin "5V") (pinfunction "P$2_5V") (pintype "bidirectional"))
      (node (ref "S1") (pin "6V") (pinfunction "P$2_6V") (pintype "bidirectional"))
      (node (ref "S1") (pin "7V") (pinfunction "P$2_7V") (pintype "bidirectional"))
      (node (ref "S1") (pin "8V") (pinfunction "P$2_8V") (pintype "bidirectional"))
      (node (ref "S1") (pin "9V") (pinfunction "P$2_9V") (pintype "bidirectional"))
    )
    (net (code "56") (name "unconnected-(CON6-Pad1.3)") (class "Default")
      (node (ref "CON6") (pin "1.3") (pinfunction "1.3_1.3") (pintype "bidirectional"))
    )
    (net (code "57") (name "unconnected-(CON6-Pad1.4)") (class "Default")
      (node (ref "CON6") (pin "1.4") (pinfunction "1.4_1.4") (pintype "bidirectional"))
    )
    (net (code "58") (name "unconnected-(CON6-Pad1.5)") (class "Default")
      (node (ref "CON6") (pin "1.5") (pinfunction "1.5_1.5") (pintype "bidirectional"))
    )
    (net (code "59") (name "unconnected-(CON6-Pad1.6)") (class "Default")
      (node (ref "CON6") (pin "1.6") (pinfunction "1.6_1.6") (pintype "bidirectional"))
    )
    (net (code "60") (name "unconnected-(CON6-Pad2.3)") (class "Default")
      (node (ref "CON6") (pin "2.3") (pinfunction "2.3_2.3") (pintype "bidirectional"))
    )
    (net (code "61") (name "unconnected-(CON6-Pad2.4)") (class "Default")
      (node (ref "CON6") (pin "2.4") (pinfunction "2.4_2.4") (pintype "bidirectional"))
    )
    (net (code "62") (name "unconnected-(CON6-Pad2.5)") (class "Default")
      (node (ref "CON6") (pin "2.5") (pinfunction "2.5_2.5") (pintype "bidirectional"))
    )
    (net (code "63") (name "unconnected-(CON6-Pad2.6)") (class "Default")
      (node (ref "CON6") (pin "2.6") (pinfunction "2.6_2.6") (pintype "bidirectional"))
    )
    (net (code "64") (name "unconnected-(IC1-(AIN0{slash}INT2)PB2-Pad42)") (class "Default")
      (node (ref "IC1") (pin "42") (pinfunction "(AIN0/INT2)PB2_42") (pintype "bidirectional"))
    )
    (net (code "65") (name "unconnected-(IC1-(ICP)PD6-Pad15)") (class "Default")
      (node (ref "IC1") (pin "15") (pinfunction "(ICP)PD6_15") (pintype "bidirectional"))
    )
    (net (code "66") (name "unconnected-(IC1-(INT0)PD2-Pad11)") (class "Default")
      (node (ref "IC1") (pin "11") (pinfunction "(INT0)PD2_11") (pintype "bidirectional"))
    )
    (net (code "67") (name "unconnected-(IC1-(INT1)PD3-Pad12)") (class "Default")
      (node (ref "IC1") (pin "12") (pinfunction "(INT1)PD3_12") (pintype "bidirectional"))
    )
    (net (code "68") (name "unconnected-(IC1-(T1)PB1-Pad41)") (class "Default")
      (node (ref "IC1") (pin "41") (pinfunction "(T1)PB1_41") (pintype "bidirectional"))
    )
    (net (code "69") (name "{slash}RESET") (class "Default")
      (node (ref "C1") (pin "1") (pinfunction "1_1") (pintype "passive"))
      (node (ref "CON5") (pin "5") (pinfunction "P$5_5") (pintype "bidirectional"))
      (node (ref "D2") (pin "A") (pinfunction "A_A") (pintype "passive"))
      (node (ref "IC1") (pin "4") (pinfunction "RESET_4") (pintype "input"))
      (node (ref "R1") (pin "1") (pinfunction "1_1") (pintype "passive"))
    )
    (net (code "70") (name "{slash}RE_RS485") (class "Default")
      (node (ref "IC1") (pin "22") (pinfunction "(TMS)PC3_22") (pintype "bidirectional"))
      (node (ref "IC5") (pin "2") (pinfunction "/RE_2") (pintype "bidirectional"))
      (node (ref "R5") (pin "1") (pinfunction "1_1") (pintype "passive"))
    )
    (net (code "71") (name "{slash}SS") (class "Default")
      (node (ref "IC1") (pin "44") (pinfunction "(SS)PB4_44") (pintype "bidirectional"))
    )
  )
)
